# chi2013.net
KiCad netlist of a schematic drawn in EAGLE
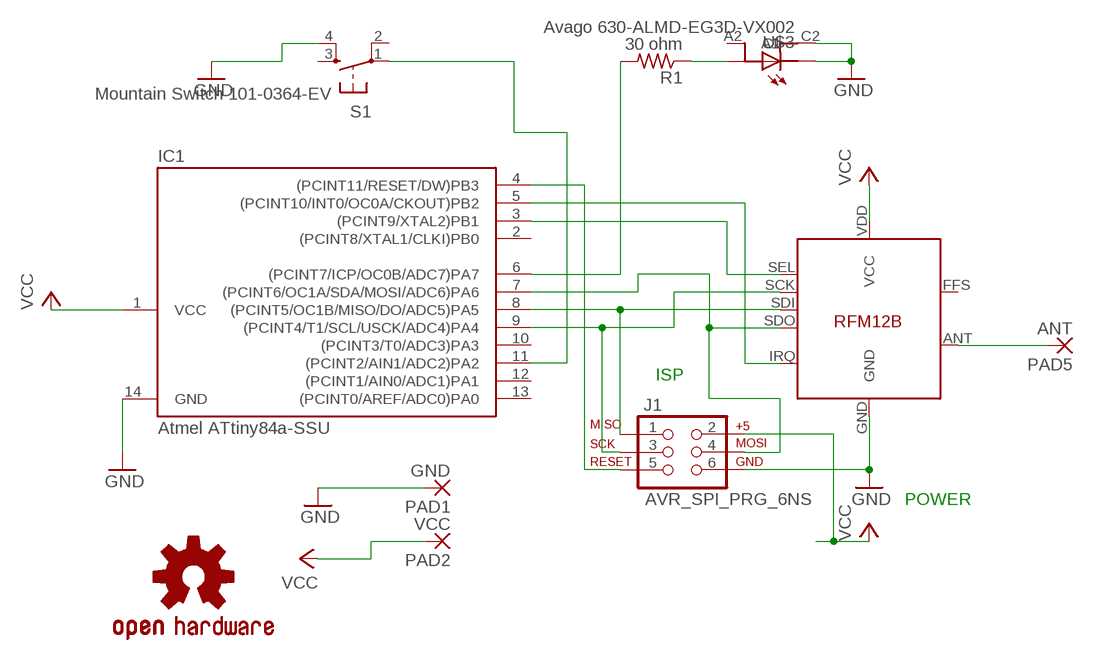
[diagram p0: schematic, sheet 1]

(export (version "E")
  (design (tool "Eeschema 10.0.6"))
  (components
    (comp (ref "IC1")
      (value "Atmel ATtiny84a-SSU")
      (footprint "eagle-import:SOIC14")
      (libsource (lib "eagle-import") (part "TINY24/44/84-SSU"))
    )
    (comp (ref "J1")
      (value "AVR_SPI_PRG_6NS")
      (footprint "eagle-import:2X3-NS")
      (libsource (lib "eagle-import") (part "AVR_SPI_PRG_6NS"))
    )
    (comp (ref "PAD1")
      (value "GND")
      (footprint "eagle-import:2,15_1,0")
      (libsource (lib "eagle-import") (part "2,15/1,0"))
    )
    (comp (ref "PAD2")
      (value "VCC")
      (footprint "eagle-import:2,15_1,0")
      (libsource (lib "eagle-import") (part "2,15/1,0"))
    )
    (comp (ref "PAD5")
      (value "ANT")
      (footprint "eagle-import:2,15_1,0")
      (libsource (lib "eagle-import") (part "2,15/1,0"))
    )
    (comp (ref "R1")
      (value "30 ohm")
      (footprint "eagle-import:R0805")
      (libsource (lib "eagle-import") (part "R-US_R0805"))
    )
    (comp (ref "RFM12B")
      (value "HopeRF RFM12B-433S1")
      (footprint "eagle-import:RFM12B-NARROW")
      (libsource (lib "eagle-import") (part "RFM12BN"))
    )
    (comp (ref "S1")
      (value "Mountain Switch 101-0364-EV")
      (footprint "eagle-import:DTSM-6")
      (libsource (lib "eagle-import") (part "DTSM-6"))
    )
    (comp (ref "U$1")
      (value "OSHW-LOGOS")
      (footprint "eagle-import:OSHW-LOGO-S")
      (libsource (lib "eagle-import") (part "OSHW-LOGOS"))
    )
    (comp (ref "U$3")
      (value "Avago 630-ALMD-EG3D-VX002")
      (footprint "eagle-import:ALMD-__3D")
      (libsource (lib "eagle-import") (part "ALMD-XX3D"))
    )
  )
  (nets
    (net (code "1") (name "GND") (class "Default")
      (node (ref "IC1") (pin "14") (pinfunction "GND_14") (pintype "power_in"))
      (node (ref "J1") (pin "6") (pinfunction "6_6") (pintype "passive"))
      (node (ref "PAD1") (pin "1") (pinfunction "P_1") (pintype "passive"))
      (node (ref "RFM12B") (pin "GND") (pinfunction "GND_GND") (pintype "power_in"))
      (node (ref "S1") (pin "4") (pinfunction "4_4") (pintype "passive"))
      (node (ref "U$3") (pin "C1") (pinfunction "C_C1") (pintype "passive"))
      (node (ref "U$3") (pin "C2") (pinfunction "C1_C2") (pintype "bidirectional"))
    )
    (net (code "2") (name "Net-(IC1-(PCINT2{slash}AIN1{slash}ADC2)PA2)") (class "Default")
      (node (ref "IC1") (pin "11") (pinfunction "(PCINT2/AIN1/ADC2)PA2_11") (pintype "bidirectional"))
      (node (ref "S1") (pin "1") (pinfunction "1_1") (pintype "passive"))
    )
    (net (code "3") (name "Net-(IC1-(PCINT4{slash}T1{slash}SCL{slash}USCK{slash}ADC4)PA4)") (class "Default")
      (node (ref "IC1") (pin "9") (pinfunction "(PCINT4/T1/SCL/USCK/ADC4)PA4_9") (pintype "bidirectional"))
      (node (ref "J1") (pin "3") (pinfunction "3_3") (pintype "passive"))
      (node (ref "RFM12B") (pin "SCK") (pinfunction "SCK_SCK") (pintype "input"))
    )
    (net (code "4") (name "Net-(IC1-(PCINT5{slash}OC1B{slash}MISO{slash}DO{slash}ADC5)PA5)") (class "Default")
      (node (ref "IC1") (pin "8") (pinfunction "(PCINT5/OC1B/MISO/DO/ADC5)PA5_8") (pintype "bidirectional"))
      (node (ref "J1") (pin "1") (pinfunction "1_1") (pintype "passive"))
      (node (ref "RFM12B") (pin "SDI") (pinfunction "SDI_SDI") (pintype "input"))
    )
    (net (code "5") (name "Net-(IC1-(PCINT6{slash}OC1A{slash}SDA{slash}MOSI{slash}ADC6)PA6)") (class "Default")
      (node (ref "IC1") (pin "7") (pinfunction "(PCINT6/OC1A/SDA/MOSI/ADC6)PA6_7") (pintype "bidirectional"))
      (node (ref "J1") (pin "4") (pinfunction "4_4") (pintype "passive"))
      (node (ref "RFM12B") (pin "SDO") (pinfunction "SDO_SDO") (pintype "output"))
    )
    (net (code "6") (name "Net-(IC1-(PCINT7{slash}ICP{slash}OC0B{slash}ADC7)PA7)") (class "Default")
      (node (ref "IC1") (pin "6") (pinfunction "(PCINT7/ICP/OC0B/ADC7)PA7_6") (pintype "bidirectional"))
      (node (ref "R1") (pin "2") (pinfunction "2_2") (pintype "passive"))
    )
    (net (code "7") (name "Net-(IC1-(PCINT9{slash}XTAL2)PB1)") (class "Default")
      (node (ref "IC1") (pin "3") (pinfunction "(PCINT9/XTAL2)PB1_3") (pintype "bidirectional"))
      (node (ref "RFM12B") (pin "SEL") (pinfunction "SEL_SEL") (pintype "input"))
    )
    (net (code "8") (name "Net-(IC1-(PCINT10{slash}INT0{slash}OC0A{slash}CKOUT)PB2)") (class "Default")
      (node (ref "IC1") (pin "5") (pinfunction "(PCINT10/INT0/OC0A/CKOUT)PB2_5") (pintype "bidirectional"))
      (node (ref "RFM12B") (pin "IRQ") (pinfunction "IRQ_IRQ") (pintype "open_collector"))
    )
    (net (code "9") (name "Net-(IC1-(PCINT11{slash}RESET{slash}DW)PB3)") (class "Default")
      (node (ref "IC1") (pin "4") (pinfunction "(PCINT11/RESET/DW)PB3_4") (pintype "bidirectional"))
      (node (ref "J1") (pin "5") (pinfunction "5_5") (pintype "passive"))
    )
    (net (code "10") (name "Net-(PAD5-P)") (class "Default")
      (node (ref "PAD5") (pin "1") (pinfunction "P_1") (pintype "passive"))
      (node (ref "RFM12B") (pin "ANT") (pinfunction "ANT_ANT") (pintype "passive"))
    )
    (net (code "11") (name "Net-(U$3-A)") (class "Default")
      (node (ref "R1") (pin "1") (pinfunction "1_1") (pintype "passive"))
      (node (ref "U$3") (pin "A1") (pinfunction "A_A1") (pintype "passive"))
    )
    (net (code "12") (name "VCC") (class "Default")
      (node (ref "IC1") (pin "1") (pinfunction "VCC_1") (pintype "power_in"))
      (node (ref "J1") (pin "2") (pinfunction "2_2") (pintype "passive"))
      (node (ref "PAD2") (pin "1") (pinfunction "P_1") (pintype "passive"))
      (node (ref "RFM12B") (pin "VDD") (pinfunction "VCC_VDD") (pintype "power_in"))
    )
    (net (code "13") (name "unconnected-(IC1-(PCINT0{slash}AREF{slash}ADC0)PA0-Pad13)") (class "Default")
      (node (ref "IC1") (pin "13") (pinfunction "(PCINT0/AREF/ADC0)PA0_13") (pintype "bidirectional"))
    )
    (net (code "14") (name "unconnected-(IC1-(PCINT1{slash}AIN0{slash}ADC1)PA1-Pad12)") (class "Default")
      (node (ref "IC1") (pin "12") (pinfunction "(PCINT1/AIN0/ADC1)PA1_12") (pintype "bidirectional"))
    )
    (net (code "15") (name "unconnected-(IC1-(PCINT3{slash}T0{slash}ADC3)PA3-Pad10)") (class "Default")
      (node (ref "IC1") (pin "10") (pinfunction "(PCINT3/T0/ADC3)PA3_10") (pintype "bidirectional"))
    )
    (net (code "16") (name "unconnected-(IC1-(PCINT8{slash}XTAL1{slash}CLKI)PB0-Pad2)") (class "Default")
      (node (ref "IC1") (pin "2") (pinfunction "(PCINT8/XTAL1/CLKI)PB0_2") (pintype "bidirectional"))
    )
    (net (code "17") (name "unconnected-(RFM12B-PadFFS)") (class "Default")
      (node (ref "RFM12B") (pin "FFS") (pinfunction "FFS_FFS") (pintype "bidirectional"))
    )
    (net (code "18") (name "unconnected-(S1-Pad2)") (class "Default")
      (node (ref "S1") (pin "2") (pinfunction "2_2") (pintype "passive"))
    )
    (net (code "19") (name "unconnected-(S1-Pad3)") (class "Default")
      (node (ref "S1") (pin "3") (pinfunction "3_3") (pintype "passive"))
    )
    (net (code "20") (name "unconnected-(U$3-A1-PadA2)") (class "Default")
      (node (ref "U$3") (pin "A2") (pinfunction "A1_A2") (pintype "bidirectional"))
    )
  )
)
